# Misc_Sensors-Encoding.net
KiCad netlist of a schematic drawn in Altium Designer
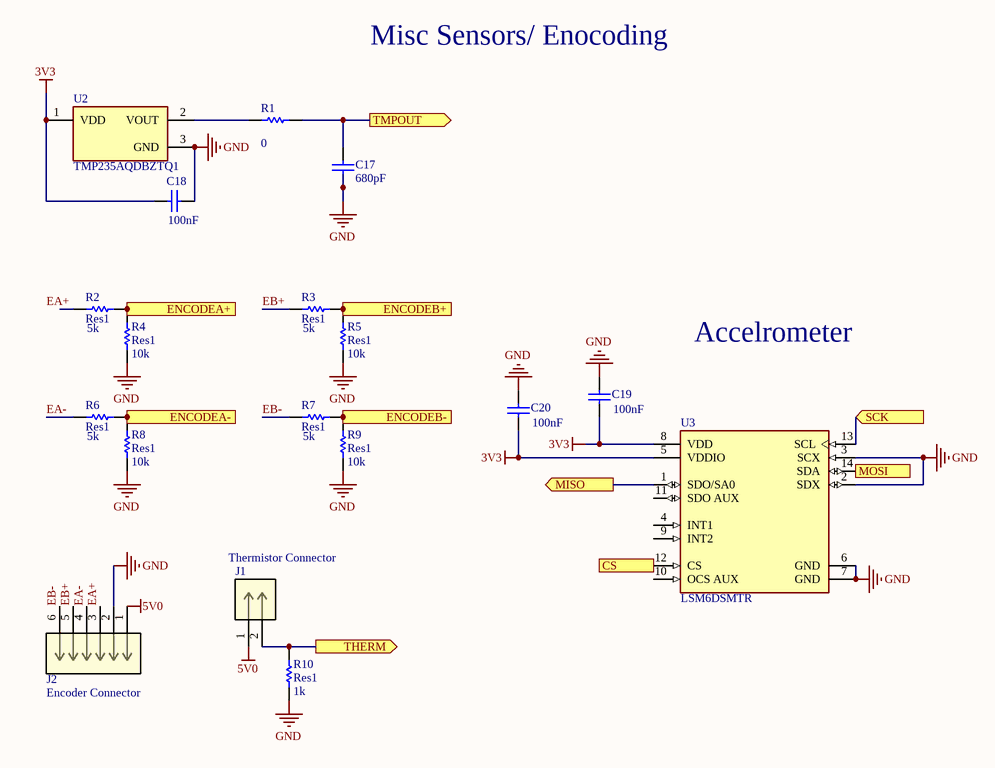
[diagram p0: Misc Sensors-Encoding.SchDoc]

(export (version "E")
  (design (tool "Eeschema 10.0.6"))
  (components
    (comp (ref "C17")
      (value "680pF")
      (footprint "1608[0603]")
      (description "Capacitor")
      (fields (field (name "Comment") "Cap") (field (name "PUBLISHER") "Altium Limited"))
      (libsource (lib "Miscellaneous Devices") (part "Cap"))
    )
    (comp (ref "C18")
      (value "100nF")
      (footprint "1608[0603]")
      (description "Capacitor")
      (fields (field (name "Comment") "Cap") (field (name "PUBLISHER") "Altium Limited"))
      (libsource (lib "Miscellaneous Devices") (part "Cap"))
    )
    (comp (ref "C19")
      (value "100nF")
      (footprint "1608[0603]")
      (description "Capacitor")
      (fields (field (name "Comment") "Cap") (field (name "PUBLISHER") "Altium Limited"))
      (libsource (lib "Miscellaneous Devices") (part "Cap"))
    )
    (comp (ref "C20")
      (value "100nF")
      (footprint "1608[0603]")
      (description "Capacitor")
      (fields (field (name "Comment") "Cap") (field (name "PUBLISHER") "Altium Limited"))
      (libsource (lib "Miscellaneous Devices") (part "Cap"))
    )
    (comp (ref "J1")
      (value "Thermistor Connector")
      (footprint "CONN_B2B-EH-A (LF)(SN)_JST")
      (description "No Description Available")
      (fields
        (field (name "MANUFACTURER_PART_NUMBER") "B2B-EH-A (LF)(SN)")
        (field (name "COPYRIGHT") "Copyright (C) 2018 Accelerated Designs. All rights reserved")
      )
      (libsource (lib "2020-09-22_22-27-35") (part "B2B-EH-A (LF)(SN)"))
    )
    (comp (ref "J2")
      (value "Encoder Connector")
      (footprint "CONN_B6B-XH-A(LF)(SN)_JST")
      (description "No Description Available")
      (fields
        (field (name "MANUFACTURER_PART_NUMBER") "B6B-XH-A(LF)(SN)")
        (field (name "COPYRIGHT") "Copyright (C) 2018 Accelerated Designs. All rights reserved")
      )
      (libsource (lib "abc encoder conn") (part "B6B-XH-A(LF)(SN)"))
    )
    (comp (ref "R1")
      (value "0")
      (footprint "0402-A")
      (description "Resistor")
      (fields (field (name "Comment") "Res1") (field (name "PUBLISHER") "Altium Limited"))
      (libsource (lib "Miscellaneous Devices") (part "Res1"))
    )
    (comp (ref "R2")
      (value "Res1")
      (footprint "0402-A")
      (description "Resistor")
      (fields (field (name "ALTIUM_VALUE") "5k") (field (name "PUBLISHER") "Altium Limited"))
      (libsource (lib "Miscellaneous Devices") (part "Res1"))
    )
    (comp (ref "R3")
      (value "Res1")
      (footprint "0402-A")
      (description "Resistor")
      (fields (field (name "ALTIUM_VALUE") "5k") (field (name "PUBLISHER") "Altium Limited"))
      (libsource (lib "Miscellaneous Devices") (part "Res1"))
    )
    (comp (ref "R4")
      (value "Res1")
      (footprint "0402-A")
      (description "Resistor")
      (fields (field (name "ALTIUM_VALUE") "10k") (field (name "PUBLISHER") "Altium Limited"))
      (libsource (lib "Miscellaneous Devices") (part "Res1"))
    )
    (comp (ref "R5")
      (value "Res1")
      (footprint "0402-A")
      (description "Resistor")
      (fields (field (name "ALTIUM_VALUE") "10k") (field (name "PUBLISHER") "Altium Limited"))
      (libsource (lib "Miscellaneous Devices") (part "Res1"))
    )
    (comp (ref "R6")
      (value "Res1")
      (footprint "0402-A")
      (description "Resistor")
      (fields (field (name "ALTIUM_VALUE") "5k") (field (name "PUBLISHER") "Altium Limited"))
      (libsource (lib "Miscellaneous Devices") (part "Res1"))
    )
    (comp (ref "R7")
      (value "Res1")
      (footprint "0402-A")
      (description "Resistor")
      (fields (field (name "ALTIUM_VALUE") "5k") (field (name "PUBLISHER") "Altium Limited"))
      (libsource (lib "Miscellaneous Devices") (part "Res1"))
    )
    (comp (ref "R8")
      (value "Res1")
      (footprint "0402-A")
      (description "Resistor")
      (fields (field (name "ALTIUM_VALUE") "10k") (field (name "PUBLISHER") "Altium Limited"))
      (libsource (lib "Miscellaneous Devices") (part "Res1"))
    )
    (comp (ref "R9")
      (value "Res1")
      (footprint "0402-A")
      (description "Resistor")
      (fields (field (name "ALTIUM_VALUE") "10k") (field (name "PUBLISHER") "Altium Limited"))
      (libsource (lib "Miscellaneous Devices") (part "Res1"))
    )
    (comp (ref "R10")
      (value "Res1")
      (footprint "0402-A")
      (description "Resistor")
      (fields (field (name "ALTIUM_VALUE") "1k") (field (name "PUBLISHER") "Altium Limited"))
      (libsource (lib "Miscellaneous Devices") (part "Res1"))
    )
    (comp (ref "U2")
      (value "TMP235AQDBZTQ1")
      (footprint "FP-DBZ0003A-MFG")
      (description "LOW-POWER HIGH-ACCURACY ANALOG O")
      (fields
        (field (name "MANUFACTURER") "Texas Instruments")
        (field (name "MANUFACTURER PART NUMBER") "TMP235A2DBZR")
      )
      (libsource (lib "Altium Content Vault") (part "1212246baba8f64ab0dd7b63bd818eb"))
    )
    (comp (ref "U3")
      (value "LSM6DSMTR")
      (footprint "FP-LGA-14L-DM00249496-MFG")
      (description "IMU ACCEL/GYRO I2C/SPI 14LGA")
      (fields
        (field (name "OCTOPART") "https://octopart.com/lsm6dsmtr-stmicroelectronics-66358194")
        (field (name "MANUFACTURER") "STMicroelectronics")
      )
      (libsource (lib "Altium Content Vault") (part "dd82ae232bae541fa9c740d21cb9072"))
    )
  )
  (nets
    (net (code "1") (name "/CS") (class "Default")
      (node (ref "U3") (pin "12") (pinfunction "CS_12") (pintype "input"))
    )
    (net (code "2") (name "/EA+") (class "Default")
      (node (ref "J2") (pin "3") (pinfunction "3_3") (pintype "passive"))
    )
    (net (code "3") (name "/EA-") (class "Default")
      (node (ref "J2") (pin "4") (pinfunction "4_4") (pintype "passive"))
      (node (ref "R6") (pin "2") (pinfunction "2_2") (pintype "passive"))
    )
    (net (code "4") (name "/EB+") (class "Default")
      (node (ref "J2") (pin "5") (pinfunction "5_5") (pintype "passive"))
      (node (ref "R3") (pin "2") (pinfunction "2_2") (pintype "passive"))
    )
    (net (code "5") (name "/EB-") (class "Default")
      (node (ref "J2") (pin "6") (pinfunction "6_6") (pintype "passive"))
      (node (ref "R7") (pin "2") (pinfunction "2_2") (pintype "passive"))
    )
    (net (code "6") (name "/ENCODEA+") (class "Default")
      (node (ref "R2") (pin "1") (pinfunction "1_1") (pintype "passive"))
      (node (ref "R4") (pin "1") (pinfunction "1_1") (pintype "passive"))
    )
    (net (code "7") (name "/ENCODEA-") (class "Default")
      (node (ref "R6") (pin "1") (pinfunction "1_1") (pintype "passive"))
      (node (ref "R8") (pin "1") (pinfunction "1_1") (pintype "passive"))
    )
    (net (code "8") (name "/ENCODEB+") (class "Default")
      (node (ref "R3") (pin "1") (pinfunction "1_1") (pintype "passive"))
      (node (ref "R5") (pin "1") (pinfunction "1_1") (pintype "passive"))
    )
    (net (code "9") (name "/ENCODEB-") (class "Default")
      (node (ref "R7") (pin "1") (pinfunction "1_1") (pintype "passive"))
      (node (ref "R9") (pin "1") (pinfunction "1_1") (pintype "passive"))
    )
    (net (code "10") (name "/MISO") (class "Default")
      (node (ref "U3") (pin "1") (pinfunction "SDO/SA0_1") (pintype "bidirectional"))
    )
    (net (code "11") (name "/MOSI") (class "Default")
      (node (ref "U3") (pin "14") (pinfunction "SDA_14") (pintype "bidirectional"))
    )
    (net (code "12") (name "/SCK") (class "Default")
      (node (ref "U3") (pin "13") (pinfunction "SCL_13") (pintype "input"))
    )
    (net (code "13") (name "/THERM") (class "Default")
      (node (ref "J1") (pin "2") (pinfunction "2_2") (pintype "passive"))
      (node (ref "R10") (pin "1") (pinfunction "1_1") (pintype "passive"))
    )
    (net (code "14") (name "/TMPOUT") (class "Default")
      (node (ref "C17") (pin "1") (pinfunction "1_1") (pintype "passive"))
      (node (ref "R1") (pin "2") (pinfunction "2_2") (pintype "passive"))
    )
    (net (code "15") (name "3V3") (class "Default")
      (node (ref "C18") (pin "1") (pinfunction "1_1") (pintype "passive"))
      (node (ref "C19") (pin "2") (pinfunction "2_2") (pintype "passive"))
      (node (ref "C20") (pin "2") (pinfunction "2_2") (pintype "passive"))
      (node (ref "U2") (pin "1") (pinfunction "VDD_1") (pintype "power_in"))
      (node (ref "U3") (pin "5") (pinfunction "VDDIO_5") (pintype "power_in"))
      (node (ref "U3") (pin "8") (pinfunction "VDD_8") (pintype "power_in"))
    )
    (net (code "16") (name "5V0") (class "Default")
      (node (ref "J1") (pin "1") (pinfunction "1_1") (pintype "passive"))
      (node (ref "J2") (pin "1") (pinfunction "1_1") (pintype "passive"))
    )
    (net (code "17") (name "GND") (class "Default")
      (node (ref "C17") (pin "2") (pinfunction "2_2") (pintype "passive"))
      (node (ref "C18") (pin "2") (pinfunction "2_2") (pintype "passive"))
      (node (ref "C19") (pin "1") (pinfunction "1_1") (pintype "passive"))
      (node (ref "C20") (pin "1") (pinfunction "1_1") (pintype "passive"))
      (node (ref "J2") (pin "2") (pinfunction "2_2") (pintype "passive"))
      (node (ref "R10") (pin "2") (pinfunction "2_2") (pintype "passive"))
      (node (ref "R4") (pin "2") (pinfunction "2_2") (pintype "passive"))
      (node (ref "R5") (pin "2") (pinfunction "2_2") (pintype "passive"))
      (node (ref "R8") (pin "2") (pinfunction "2_2") (pintype "passive"))
      (node (ref "R9") (pin "2") (pinfunction "2_2") (pintype "passive"))
      (node (ref "U2") (pin "3") (pinfunction "GND_3") (pintype "power_in"))
      (node (ref "U3") (pin "2") (pinfunction "SDX_2") (pintype "bidirectional"))
      (node (ref "U3") (pin "3") (pinfunction "SCX_3") (pintype "input"))
      (node (ref "U3") (pin "6") (pinfunction "GND_6") (pintype "power_in"))
      (node (ref "U3") (pin "7") (pinfunction "GND_7") (pintype "power_in"))
    )
    (net (code "18") (name "Net-(U2-VOUT)") (class "Default")
      (node (ref "R1") (pin "1") (pinfunction "1_1") (pintype "passive"))
      (node (ref "U2") (pin "2") (pinfunction "VOUT_2") (pintype "passive"))
    )
    (net (code "19") (name "unconnected-(R2-Pad2)") (class "Default")
      (node (ref "R2") (pin "2") (pinfunction "2_2") (pintype "passive"))
    )
    (net (code "20") (name "unconnected-(U3-INT1-Pad4)") (class "Default")
      (node (ref "U3") (pin "4") (pinfunction "INT1_4") (pintype "input"))
    )
    (net (code "21") (name "unconnected-(U3-INT2-Pad9)") (class "Default")
      (node (ref "U3") (pin "9") (pinfunction "INT2_9") (pintype "input"))
    )
    (net (code "22") (name "unconnected-(U3-OCS_AUX-Pad10)") (class "Default")
      (node (ref "U3") (pin "10") (pinfunction "OCS_AUX_10") (pintype "input"))
    )
    (net (code "23") (name "unconnected-(U3-SDO_AUX-Pad11)") (class "Default")
      (node (ref "U3") (pin "11") (pinfunction "SDO_AUX_11") (pintype "bidirectional"))
    )
  )
)
